# TOP.net
KiCad netlist of a schematic drawn in Altium Designer
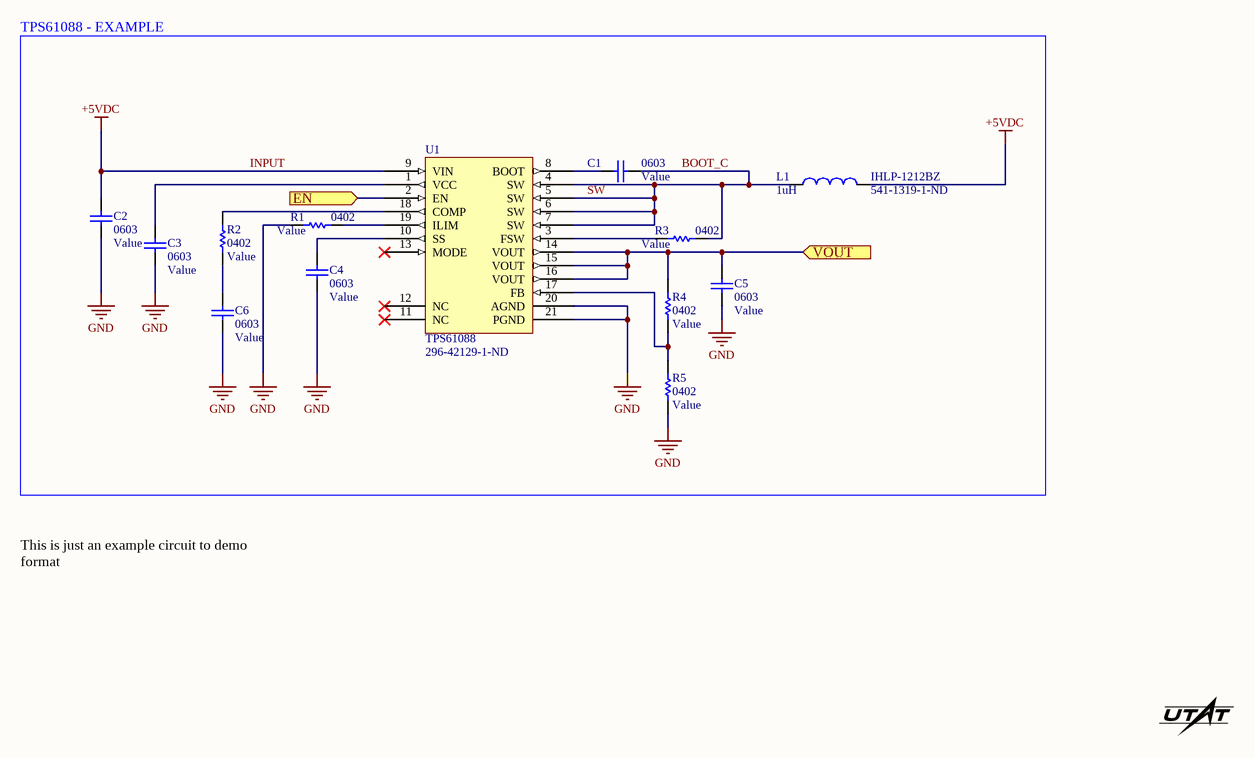
[diagram p0: TOP.SchDoc]

(export (version "E")
  (design (tool "Eeschema 10.0.6"))
  (components
    (comp (ref "C1")
      (value "0603")
      (footprint "CAP0603R")
      (description "0603 capacitor")
      (fields (field (name "ALTIUM_VALUE") "Value"))
      (libsource (lib "heron-general") (part "CAP0603"))
    )
    (comp (ref "C2")
      (value "0603")
      (footprint "CAP0603R")
      (description "0603 capacitor")
      (fields (field (name "ALTIUM_VALUE") "Value"))
      (libsource (lib "heron-general") (part "CAP0603"))
    )
    (comp (ref "C3")
      (value "0603")
      (footprint "CAP0603R")
      (description "0603 capacitor")
      (fields (field (name "ALTIUM_VALUE") "Value"))
      (libsource (lib "heron-general") (part "CAP0603"))
    )
    (comp (ref "C4")
      (value "0603")
      (footprint "CAP0603R")
      (description "0603 capacitor")
      (fields (field (name "ALTIUM_VALUE") "Value"))
      (libsource (lib "heron-general") (part "CAP0603"))
    )
    (comp (ref "C5")
      (value "0603")
      (footprint "CAP0603R")
      (description "0603 capacitor")
      (fields (field (name "ALTIUM_VALUE") "Value"))
      (libsource (lib "heron-general") (part "CAP0603"))
    )
    (comp (ref "C6")
      (value "0603")
      (footprint "CAP0603R")
      (description "0603 capacitor")
      (fields (field (name "ALTIUM_VALUE") "Value"))
      (libsource (lib "heron-general") (part "CAP0603"))
    )
    (comp (ref "L1")
      (value "IHLP-1212BZ")
      (footprint "IHLP-1212BZ")
      (description "1µH Shielded Molded Inductor 5A 24mOhm Max Nonstandard")
      (fields
        (field (name "MANUFACTURER") "Vishay Dale")
        (field (name "MANUFACTURER PART NUMBER") "IHLP1212BZER1R0M11")
        (field (name "INDUCTANCE") "1uH")
        (field (name "SUPPLIER PART NUMBER 1") "541-1319-1-ND")
      )
      (libsource (lib "heron-general") (part "IND_IHLP-1212BZ"))
    )
    (comp (ref "R1")
      (value "0402")
      (footprint "RES0402R")
      (description "0402 resistor")
      (fields (field (name "ALTIUM_VALUE") "Value"))
      (libsource (lib "heron-general") (part "RES0402"))
    )
    (comp (ref "R2")
      (value "0402")
      (footprint "RES0402R")
      (description "0402 resistor")
      (fields (field (name "ALTIUM_VALUE") "Value"))
      (libsource (lib "heron-general") (part "RES0402"))
    )
    (comp (ref "R3")
      (value "0402")
      (footprint "RES0402R")
      (description "0402 resistor")
      (fields (field (name "ALTIUM_VALUE") "Value"))
      (libsource (lib "heron-general") (part "RES0402"))
    )
    (comp (ref "R4")
      (value "0402")
      (footprint "RES0402R")
      (description "0402 resistor")
      (fields (field (name "ALTIUM_VALUE") "Value"))
      (libsource (lib "heron-general") (part "RES0402"))
    )
    (comp (ref "R5")
      (value "0402")
      (footprint "RES0402R")
      (description "0402 resistor")
      (fields (field (name "ALTIUM_VALUE") "Value"))
      (libsource (lib "heron-general") (part "RES0402"))
    )
    (comp (ref "U1")
      (value "TPS61088")
      (footprint "QFN50P450X350X100-21N")
      (description "Boost converter")
      (fields (field (name "SUPPLIER PART NUMBER 1") "296-42129-1-ND"))
      (libsource (lib "heron-general") (part "TPS61088"))
    )
  )
  (nets
    (net (code "1") (name "+5VDC") (class "Default")
      (node (ref "C2") (pin "1") (pinfunction "1_1") (pintype "passive"))
      (node (ref "L1") (pin "2") (pinfunction "2_2") (pintype "passive"))
      (node (ref "U1") (pin "9") (pinfunction "VIN_9") (pintype "input"))
    )
    (net (code "2") (name "/BOOT_C") (class "Default")
      (node (ref "C1") (pin "2") (pinfunction "2_2") (pintype "passive"))
      (node (ref "L1") (pin "1") (pinfunction "1_1") (pintype "passive"))
      (node (ref "R3") (pin "2") (pinfunction "2_2") (pintype "passive"))
      (node (ref "U1") (pin "4") (pinfunction "SW_4") (pintype "input"))
      (node (ref "U1") (pin "5") (pinfunction "SW_5") (pintype "input"))
      (node (ref "U1") (pin "6") (pinfunction "SW_6") (pintype "input"))
      (node (ref "U1") (pin "7") (pinfunction "SW_7") (pintype "input"))
    )
    (net (code "3") (name "/EN") (class "Default")
      (node (ref "U1") (pin "2") (pinfunction "EN_2") (pintype "input"))
    )
    (net (code "4") (name "/VOUT") (class "Default")
      (node (ref "C5") (pin "2") (pinfunction "2_2") (pintype "passive"))
      (node (ref "R4") (pin "2") (pinfunction "2_2") (pintype "passive"))
      (node (ref "U1") (pin "14") (pinfunction "VOUT_14") (pintype "output"))
      (node (ref "U1") (pin "15") (pinfunction "VOUT_15") (pintype "output"))
      (node (ref "U1") (pin "16") (pinfunction "VOUT_16") (pintype "output"))
    )
    (net (code "5") (name "GND") (class "Default")
      (node (ref "C2") (pin "2") (pinfunction "2_2") (pintype "passive"))
      (node (ref "C3") (pin "1") (pinfunction "1_1") (pintype "passive"))
      (node (ref "C4") (pin "1") (pinfunction "1_1") (pintype "passive"))
      (node (ref "C5") (pin "1") (pinfunction "1_1") (pintype "passive"))
      (node (ref "C6") (pin "1") (pinfunction "1_1") (pintype "passive"))
      (node (ref "R1") (pin "1") (pinfunction "1_1") (pintype "passive"))
      (node (ref "R5") (pin "1") (pinfunction "1_1") (pintype "passive"))
      (node (ref "U1") (pin "20") (pinfunction "AGND_20") (pintype "power_in"))
      (node (ref "U1") (pin "21") (pinfunction "PGND_21") (pintype "power_in"))
    )
    (net (code "6") (name "Net-(C6-Pad2)") (class "Default")
      (node (ref "C6") (pin "2") (pinfunction "2_2") (pintype "passive"))
      (node (ref "R2") (pin "1") (pinfunction "1_1") (pintype "passive"))
    )
    (net (code "7") (name "Net-(U1-BOOT)") (class "Default")
      (node (ref "C1") (pin "1") (pinfunction "1_1") (pintype "passive"))
      (node (ref "U1") (pin "8") (pinfunction "BOOT_8") (pintype "output"))
    )
    (net (code "8") (name "Net-(U1-COMP)") (class "Default")
      (node (ref "R2") (pin "2") (pinfunction "2_2") (pintype "passive"))
      (node (ref "U1") (pin "18") (pinfunction "COMP_18") (pintype "output"))
    )
    (net (code "9") (name "Net-(U1-FB)") (class "Default")
      (node (ref "R4") (pin "1") (pinfunction "1_1") (pintype "passive"))
      (node (ref "R5") (pin "2") (pinfunction "2_2") (pintype "passive"))
      (node (ref "U1") (pin "17") (pinfunction "FB_17") (pintype "input"))
    )
    (net (code "10") (name "Net-(U1-FSW)") (class "Default")
      (node (ref "R3") (pin "1") (pinfunction "1_1") (pintype "passive"))
      (node (ref "U1") (pin "3") (pinfunction "FSW_3") (pintype "input"))
    )
    (net (code "11") (name "Net-(U1-ILIM)") (class "Default")
      (node (ref "R1") (pin "2") (pinfunction "2_2") (pintype "passive"))
      (node (ref "U1") (pin "19") (pinfunction "ILIM_19") (pintype "output"))
    )
    (net (code "12") (name "Net-(U1-SS)") (class "Default")
      (node (ref "C4") (pin "2") (pinfunction "2_2") (pintype "passive"))
      (node (ref "U1") (pin "10") (pinfunction "SS_10") (pintype "output"))
    )
    (net (code "13") (name "Net-(U1-VCC)") (class "Default")
      (node (ref "C3") (pin "2") (pinfunction "2_2") (pintype "passive"))
      (node (ref "U1") (pin "1") (pinfunction "VCC_1") (pintype "output"))
    )
    (net (code "14") (name "unconnected-(U1-MODE-Pad13)") (class "Default")
      (node (ref "U1") (pin "13") (pinfunction "MODE_13") (pintype "input+no_connect"))
    )
    (net (code "15") (name "unconnected-(U1-NC-Pad11)") (class "Default")
      (node (ref "U1") (pin "11") (pinfunction "NC_11") (pintype "passive+no_connect"))
    )
    (net (code "16") (name "unconnected-(U1-NC-Pad12)") (class "Default")
      (node (ref "U1") (pin "12") (pinfunction "NC_12") (pintype "passive+no_connect"))
    )
  )
)
